# Card4to16.net
KiCad netlist of a schematic drawn in EAGLE
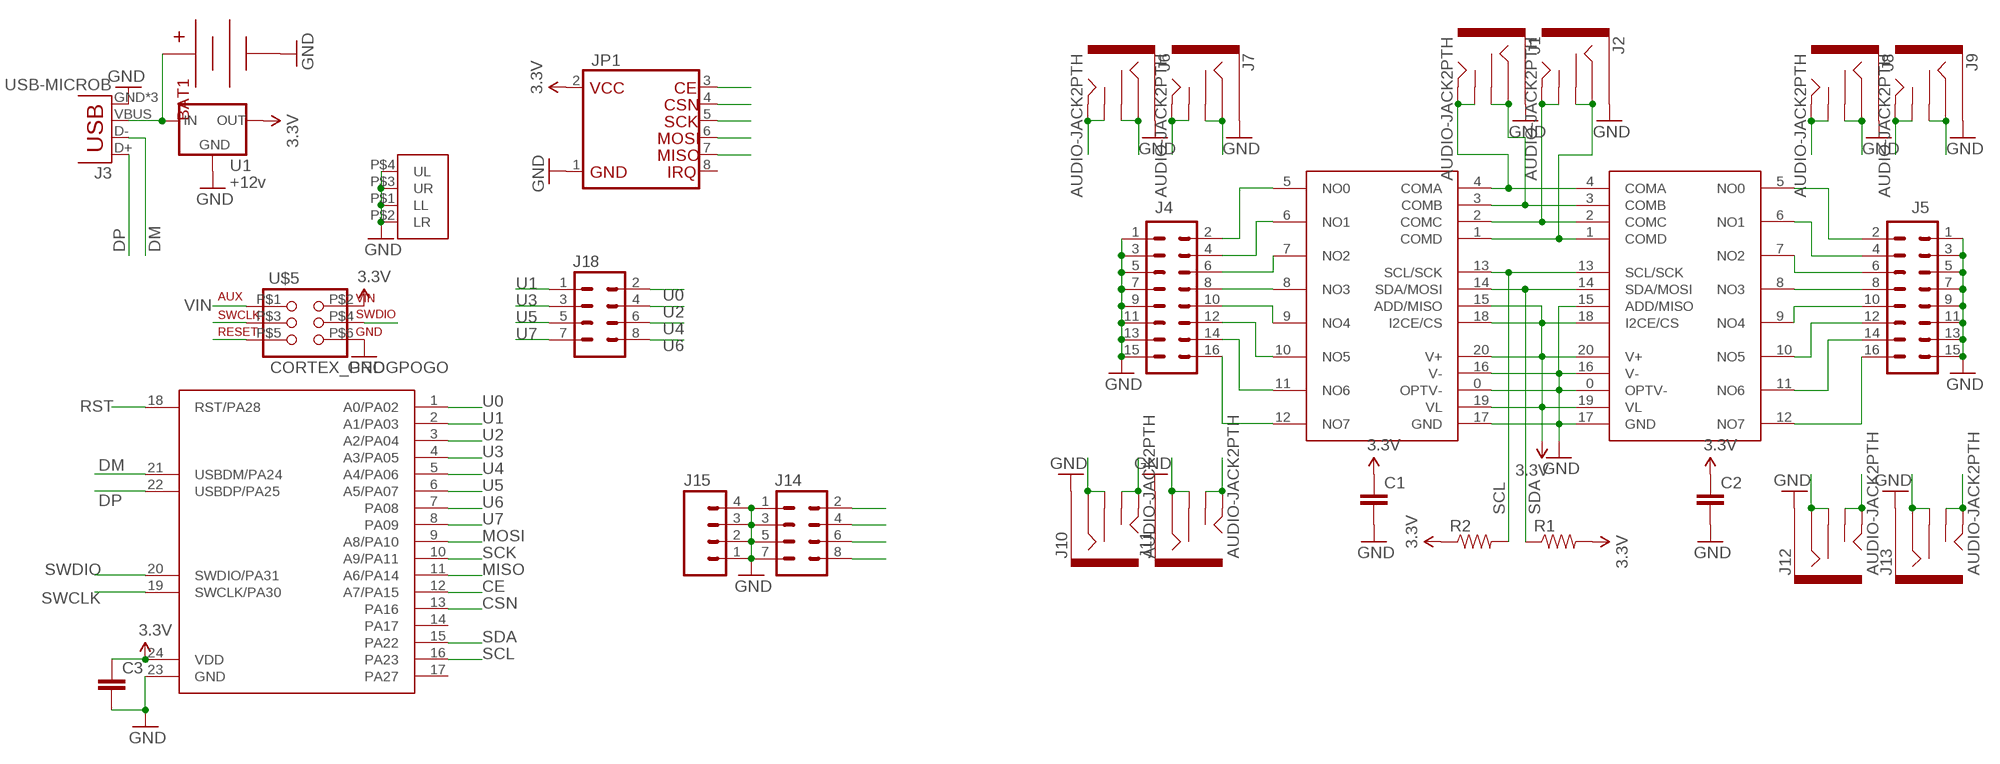
[diagram p0: schematic, sheet 1]

(export (version "E")
  (design (tool "Eeschema 10.0.6"))
  (components
    (comp (ref "BAT1")
      (value "9VHOLDERCLIPS")
      (footprint "eagle-import:BSPC9V")
      (libsource (lib "eagle-import") (part "9VHOLDERCLIPS"))
    )
    (comp (ref "C1")
      (value "CAP0805")
      (footprint "eagle-import:0805")
      (libsource (lib "eagle-import") (part "CAP0805"))
    )
    (comp (ref "C2")
      (value "CAP0805")
      (footprint "eagle-import:0805")
      (libsource (lib "eagle-import") (part "CAP0805"))
    )
    (comp (ref "C3")
      (value "CAP0805")
      (footprint "eagle-import:0805")
      (libsource (lib "eagle-import") (part "CAP0805"))
    )
    (comp (ref "J1")
      (value "AUDIO-JACK2PTH")
      (footprint "eagle-import:AUDIO-JACK")
      (libsource (lib "eagle-import") (part "AUDIO-JACK2PTH"))
    )
    (comp (ref "J2")
      (value "AUDIO-JACK2PTH")
      (footprint "eagle-import:AUDIO-JACK")
      (libsource (lib "eagle-import") (part "AUDIO-JACK2PTH"))
    )
    (comp (ref "J3")
      (value "USB-MICROB")
      (footprint "eagle-import:USB-MICROB")
      (libsource (lib "eagle-import") (part "USB-MICROB"))
    )
    (comp (ref "J4")
      (value "M08X2")
      (footprint "eagle-import:2X8")
      (libsource (lib "eagle-import") (part "M08X2"))
    )
    (comp (ref "J5")
      (value "M08X2")
      (footprint "eagle-import:2X8")
      (libsource (lib "eagle-import") (part "M08X2"))
    )
    (comp (ref "J6")
      (value "AUDIO-JACK2PTH")
      (footprint "eagle-import:AUDIO-JACK")
      (libsource (lib "eagle-import") (part "AUDIO-JACK2PTH"))
    )
    (comp (ref "J7")
      (value "AUDIO-JACK2PTH")
      (footprint "eagle-import:AUDIO-JACK")
      (libsource (lib "eagle-import") (part "AUDIO-JACK2PTH"))
    )
    (comp (ref "J8")
      (value "AUDIO-JACK2PTH")
      (footprint "eagle-import:AUDIO-JACK")
      (libsource (lib "eagle-import") (part "AUDIO-JACK2PTH"))
    )
    (comp (ref "J9")
      (value "AUDIO-JACK2PTH")
      (footprint "eagle-import:AUDIO-JACK")
      (libsource (lib "eagle-import") (part "AUDIO-JACK2PTH"))
    )
    (comp (ref "J10")
      (value "AUDIO-JACK2PTH")
      (footprint "eagle-import:AUDIO-JACK")
      (libsource (lib "eagle-import") (part "AUDIO-JACK2PTH"))
    )
    (comp (ref "J11")
      (value "AUDIO-JACK2PTH")
      (footprint "eagle-import:AUDIO-JACK")
      (libsource (lib "eagle-import") (part "AUDIO-JACK2PTH"))
    )
    (comp (ref "J12")
      (value "AUDIO-JACK2PTH")
      (footprint "eagle-import:AUDIO-JACK")
      (libsource (lib "eagle-import") (part "AUDIO-JACK2PTH"))
    )
    (comp (ref "J13")
      (value "AUDIO-JACK2PTH")
      (footprint "eagle-import:AUDIO-JACK")
      (libsource (lib "eagle-import") (part "AUDIO-JACK2PTH"))
    )
    (comp (ref "J14")
      (value "M04X2")
      (footprint "eagle-import:2X4")
      (libsource (lib "eagle-import") (part "M04X2"))
    )
    (comp (ref "J15")
      (value "M04PTH")
      (footprint "eagle-import:1X04")
      (libsource (lib "eagle-import") (part "M04PTH"))
    )
    (comp (ref "J18")
      (value "M04X2")
      (footprint "eagle-import:2X4")
      (libsource (lib "eagle-import") (part "M04X2"))
    )
    (comp (ref "JP1")
      (value "NRF24L01+SHORT_FLUSH")
      (footprint "eagle-import:NRF24L01SHORT")
      (libsource (lib "eagle-import") (part "NRF24L01+SHORT_FLUSH"))
    )
    (comp (ref "R1")
      (value "RESISTOR0603-RES")
      (footprint "eagle-import:0603-RES")
      (libsource (lib "eagle-import") (part "RESISTOR0603-RES"))
    )
    (comp (ref "R2")
      (value "RESISTOR0603-RES")
      (footprint "eagle-import:0603-RES")
      (libsource (lib "eagle-import") (part "RESISTOR0603-RES"))
    )
    (comp (ref "U$1")
      (value "MAX14724ETP+QFN")
      (footprint "eagle-import:QFN20_4X4")
      (libsource (lib "eagle-import") (part "MAX14724ETP+QFN"))
    )
    (comp (ref "U$2")
      (value "MAX14724ETP+QFN")
      (footprint "eagle-import:QFN20_4X4")
      (libsource (lib "eagle-import") (part "MAX14724ETP+QFN"))
    )
    (comp (ref "U$3")
      (value "ATSAMD11D14A-M")
      (footprint "eagle-import:QFN24_4X4")
      (libsource (lib "eagle-import") (part "ATSAMD11D14A-M"))
    )
    (comp (ref "U$4")
      (value "CARD_HOLESHOLES")
      (footprint "eagle-import:IEC-7810_ID-1_HOLES")
      (libsource (lib "eagle-import") (part "CARD_HOLESHOLES"))
    )
    (comp (ref "U$5")
      (value "CORTEX_PROGPOGO")
      (footprint "eagle-import:2X3_MAX")
      (libsource (lib "eagle-import") (part "CORTEX_PROGPOGO"))
    )
    (comp (ref "U1")
      (value "+12v")
      (footprint "eagle-import:TO-252")
      (libsource (lib "eagle-import") (part "V_REG_78XX7812"))
    )
  )
  (nets
    (net (code "1") (name "/CE") (class "Default")
      (node (ref "JP1") (pin "3") (pinfunction "CE_3") (pintype "passive"))
      (node (ref "U$3") (pin "12") (pinfunction "A7/PA15_12") (pintype "bidirectional"))
    )
    (net (code "2") (name "/COMA") (class "Default")
      (node (ref "J1") (pin "TIP") (pinfunction "TIP_TIP") (pintype "bidirectional"))
      (node (ref "J1") (pin "TSH") (pinfunction "TSH_TSH") (pintype "bidirectional"))
      (node (ref "J14") (pin "2") (pinfunction "2_2") (pintype "passive"))
      (node (ref "U$1") (pin "4") (pinfunction "COMA_4") (pintype "bidirectional"))
      (node (ref "U$2") (pin "4") (pinfunction "COMA_4") (pintype "bidirectional"))
    )
    (net (code "3") (name "/COMB") (class "Default")
      (node (ref "J1") (pin "RING") (pinfunction "RING_RING") (pintype "bidirectional"))
      (node (ref "J1") (pin "RSH") (pinfunction "RSH_RSH") (pintype "bidirectional"))
      (node (ref "J14") (pin "4") (pinfunction "4_4") (pintype "passive"))
      (node (ref "U$1") (pin "3") (pinfunction "COMB_3") (pintype "bidirectional"))
      (node (ref "U$2") (pin "3") (pinfunction "COMB_3") (pintype "bidirectional"))
    )
    (net (code "4") (name "/COMC") (class "Default")
      (node (ref "J14") (pin "6") (pinfunction "6_6") (pintype "passive"))
      (node (ref "J2") (pin "TIP") (pinfunction "TIP_TIP") (pintype "bidirectional"))
      (node (ref "J2") (pin "TSH") (pinfunction "TSH_TSH") (pintype "bidirectional"))
      (node (ref "U$1") (pin "2") (pinfunction "COMC_2") (pintype "bidirectional"))
      (node (ref "U$2") (pin "2") (pinfunction "COMC_2") (pintype "bidirectional"))
    )
    (net (code "5") (name "/COMD") (class "Default")
      (node (ref "J14") (pin "8") (pinfunction "8_8") (pintype "passive"))
      (node (ref "J2") (pin "RING") (pinfunction "RING_RING") (pintype "bidirectional"))
      (node (ref "J2") (pin "RSH") (pinfunction "RSH_RSH") (pintype "bidirectional"))
      (node (ref "U$1") (pin "1") (pinfunction "COMD_1") (pintype "bidirectional"))
      (node (ref "U$2") (pin "1") (pinfunction "COMD_1") (pintype "bidirectional"))
    )
    (net (code "6") (name "/CSN") (class "Default")
      (node (ref "JP1") (pin "4") (pinfunction "CSN_4") (pintype "passive"))
      (node (ref "U$3") (pin "13") (pinfunction "PA16_13") (pintype "bidirectional"))
    )
    (net (code "7") (name "/DM") (class "Default")
      (node (ref "J3") (pin "D-") (pinfunction "D-_D-") (pintype "bidirectional"))
      (node (ref "U$3") (pin "21") (pinfunction "USBDM/PA24_21") (pintype "bidirectional"))
    )
    (net (code "8") (name "/DP") (class "Default")
      (node (ref "J3") (pin "D+") (pinfunction "D+_D+") (pintype "bidirectional"))
      (node (ref "U$3") (pin "22") (pinfunction "USBDP/PA25_22") (pintype "bidirectional"))
    )
    (net (code "9") (name "/MISO") (class "Default")
      (node (ref "JP1") (pin "7") (pinfunction "MISO_7") (pintype "passive"))
      (node (ref "U$3") (pin "11") (pinfunction "A6/PA14_11") (pintype "bidirectional"))
    )
    (net (code "10") (name "/MOSI") (class "Default")
      (node (ref "JP1") (pin "6") (pinfunction "MOSI_6") (pintype "passive"))
      (node (ref "U$3") (pin "9") (pinfunction "A8/PA10_9") (pintype "bidirectional"))
    )
    (net (code "11") (name "/OUT1") (class "Default")
      (node (ref "J10") (pin "RING") (pinfunction "RING_RING") (pintype "bidirectional"))
      (node (ref "J10") (pin "RSH") (pinfunction "RSH_RSH") (pintype "bidirectional"))
      (node (ref "J4") (pin "2") (pinfunction "2_2") (pintype "passive"))
      (node (ref "U$1") (pin "5") (pinfunction "NO0_5") (pintype "bidirectional"))
    )
    (net (code "12") (name "/OUT2") (class "Default")
      (node (ref "J10") (pin "TIP") (pinfunction "TIP_TIP") (pintype "bidirectional"))
      (node (ref "J10") (pin "TSH") (pinfunction "TSH_TSH") (pintype "bidirectional"))
      (node (ref "J4") (pin "4") (pinfunction "4_4") (pintype "passive"))
      (node (ref "U$1") (pin "6") (pinfunction "NO1_6") (pintype "bidirectional"))
    )
    (net (code "13") (name "/OUT3") (class "Default")
      (node (ref "J11") (pin "RING") (pinfunction "RING_RING") (pintype "bidirectional"))
      (node (ref "J11") (pin "RSH") (pinfunction "RSH_RSH") (pintype "bidirectional"))
      (node (ref "J4") (pin "6") (pinfunction "6_6") (pintype "passive"))
      (node (ref "U$1") (pin "7") (pinfunction "NO2_7") (pintype "bidirectional"))
    )
    (net (code "14") (name "/OUT4") (class "Default")
      (node (ref "J11") (pin "TIP") (pinfunction "TIP_TIP") (pintype "bidirectional"))
      (node (ref "J11") (pin "TSH") (pinfunction "TSH_TSH") (pintype "bidirectional"))
      (node (ref "J4") (pin "8") (pinfunction "8_8") (pintype "passive"))
      (node (ref "U$1") (pin "8") (pinfunction "NO3_8") (pintype "bidirectional"))
    )
    (net (code "15") (name "/OUT5") (class "Default")
      (node (ref "J12") (pin "RING") (pinfunction "RING_RING") (pintype "bidirectional"))
      (node (ref "J12") (pin "RSH") (pinfunction "RSH_RSH") (pintype "bidirectional"))
      (node (ref "J4") (pin "10") (pinfunction "10_10") (pintype "passive"))
      (node (ref "U$1") (pin "9") (pinfunction "NO4_9") (pintype "bidirectional"))
    )
    (net (code "16") (name "/OUT6") (class "Default")
      (node (ref "J12") (pin "TIP") (pinfunction "TIP_TIP") (pintype "bidirectional"))
      (node (ref "J12") (pin "TSH") (pinfunction "TSH_TSH") (pintype "bidirectional"))
      (node (ref "J4") (pin "12") (pinfunction "12_12") (pintype "passive"))
      (node (ref "U$1") (pin "10") (pinfunction "NO5_10") (pintype "bidirectional"))
    )
    (net (code "17") (name "/OUT7") (class "Default")
      (node (ref "J13") (pin "RING") (pinfunction "RING_RING") (pintype "bidirectional"))
      (node (ref "J13") (pin "RSH") (pinfunction "RSH_RSH") (pintype "bidirectional"))
      (node (ref "J4") (pin "14") (pinfunction "14_14") (pintype "passive"))
      (node (ref "U$1") (pin "11") (pinfunction "NO6_11") (pintype "bidirectional"))
    )
    (net (code "18") (name "/OUT8") (class "Default")
      (node (ref "J13") (pin "TIP") (pinfunction "TIP_TIP") (pintype "bidirectional"))
      (node (ref "J13") (pin "TSH") (pinfunction "TSH_TSH") (pintype "bidirectional"))
      (node (ref "J4") (pin "16") (pinfunction "16_16") (pintype "passive"))
      (node (ref "U$1") (pin "12") (pinfunction "NO7_12") (pintype "bidirectional"))
    )
    (net (code "19") (name "/OUT9") (class "Default")
      (node (ref "J5") (pin "2") (pinfunction "2_2") (pintype "passive"))
      (node (ref "J6") (pin "RING") (pinfunction "RING_RING") (pintype "bidirectional"))
      (node (ref "J6") (pin "RSH") (pinfunction "RSH_RSH") (pintype "bidirectional"))
      (node (ref "U$2") (pin "5") (pinfunction "NO0_5") (pintype "bidirectional"))
    )
    (net (code "20") (name "/OUT10") (class "Default")
      (node (ref "J5") (pin "4") (pinfunction "4_4") (pintype "passive"))
      (node (ref "J6") (pin "TIP") (pinfunction "TIP_TIP") (pintype "bidirectional"))
      (node (ref "J6") (pin "TSH") (pinfunction "TSH_TSH") (pintype "bidirectional"))
      (node (ref "U$2") (pin "6") (pinfunction "NO1_6") (pintype "bidirectional"))
    )
    (net (code "21") (name "/OUT11") (class "Default")
      (node (ref "J5") (pin "6") (pinfunction "6_6") (pintype "passive"))
      (node (ref "J7") (pin "RING") (pinfunction "RING_RING") (pintype "bidirectional"))
      (node (ref "J7") (pin "RSH") (pinfunction "RSH_RSH") (pintype "bidirectional"))
      (node (ref "U$2") (pin "7") (pinfunction "NO2_7") (pintype "bidirectional"))
    )
    (net (code "22") (name "/OUT12") (class "Default")
      (node (ref "J5") (pin "8") (pinfunction "8_8") (pintype "passive"))
      (node (ref "J7") (pin "TIP") (pinfunction "TIP_TIP") (pintype "bidirectional"))
      (node (ref "J7") (pin "TSH") (pinfunction "TSH_TSH") (pintype "bidirectional"))
      (node (ref "U$2") (pin "8") (pinfunction "NO3_8") (pintype "bidirectional"))
    )
    (net (code "23") (name "/OUT13") (class "Default")
      (node (ref "J5") (pin "10") (pinfunction "10_10") (pintype "passive"))
      (node (ref "J8") (pin "RING") (pinfunction "RING_RING") (pintype "bidirectional"))
      (node (ref "J8") (pin "RSH") (pinfunction "RSH_RSH") (pintype "bidirectional"))
      (node (ref "U$2") (pin "9") (pinfunction "NO4_9") (pintype "bidirectional"))
    )
    (net (code "24") (name "/OUT14") (class "Default")
      (node (ref "J5") (pin "12") (pinfunction "12_12") (pintype "passive"))
      (node (ref "J8") (pin "TIP") (pinfunction "TIP_TIP") (pintype "bidirectional"))
      (node (ref "J8") (pin "TSH") (pinfunction "TSH_TSH") (pintype "bidirectional"))
      (node (ref "U$2") (pin "10") (pinfunction "NO5_10") (pintype "bidirectional"))
    )
    (net (code "25") (name "/OUT15") (class "Default")
      (node (ref "J5") (pin "14") (pinfunction "14_14") (pintype "passive"))
      (node (ref "J9") (pin "RING") (pinfunction "RING_RING") (pintype "bidirectional"))
      (node (ref "J9") (pin "RSH") (pinfunction "RSH_RSH") (pintype "bidirectional"))
      (node (ref "U$2") (pin "11") (pinfunction "NO6_11") (pintype "bidirectional"))
    )
    (net (code "26") (name "/OUT16") (class "Default")
      (node (ref "J5") (pin "16") (pinfunction "16_16") (pintype "passive"))
      (node (ref "J9") (pin "TIP") (pinfunction "TIP_TIP") (pintype "bidirectional"))
      (node (ref "J9") (pin "TSH") (pinfunction "TSH_TSH") (pintype "bidirectional"))
      (node (ref "U$2") (pin "12") (pinfunction "NO7_12") (pintype "bidirectional"))
    )
    (net (code "27") (name "/RST") (class "Default")
      (node (ref "U$3") (pin "18") (pinfunction "RST/PA28_18") (pintype "bidirectional"))
      (node (ref "U$5") (pin "P$5") (pinfunction "RST_P$5") (pintype "passive"))
    )
    (net (code "28") (name "/SCK") (class "Default")
      (node (ref "JP1") (pin "5") (pinfunction "SCK_5") (pintype "passive"))
      (node (ref "U$3") (pin "10") (pinfunction "A9/PA11_10") (pintype "bidirectional"))
    )
    (net (code "29") (name "/SCL") (class "Default")
      (node (ref "R2") (pin "2") (pinfunction "2_2") (pintype "passive"))
      (node (ref "U$1") (pin "13") (pinfunction "SCL/SCK_13") (pintype "bidirectional"))
      (node (ref "U$2") (pin "13") (pinfunction "SCL/SCK_13") (pintype "bidirectional"))
      (node (ref "U$3") (pin "16") (pinfunction "PA23_16") (pintype "bidirectional"))
    )
    (net (code "30") (name "/SDA") (class "Default")
      (node (ref "R1") (pin "1") (pinfunction "1_1") (pintype "passive"))
      (node (ref "U$1") (pin "14") (pinfunction "SDA/MOSI_14") (pintype "bidirectional"))
      (node (ref "U$2") (pin "14") (pinfunction "SDA/MOSI_14") (pintype "bidirectional"))
      (node (ref "U$3") (pin "15") (pinfunction "PA22_15") (pintype "bidirectional"))
    )
    (net (code "31") (name "/SWCLK") (class "Default")
      (node (ref "U$3") (pin "19") (pinfunction "SWCLK/PA30_19") (pintype "bidirectional"))
      (node (ref "U$5") (pin "P$3") (pinfunction "SWCLK_P$3") (pintype "passive"))
    )
    (net (code "32") (name "/SWDIO") (class "Default")
      (node (ref "U$3") (pin "20") (pinfunction "SWDIO/PA31_20") (pintype "bidirectional"))
      (node (ref "U$5") (pin "P$4") (pinfunction "SWDIO_P$4") (pintype "passive"))
    )
    (net (code "33") (name "/U0") (class "Default")
      (node (ref "J18") (pin "2") (pinfunction "2_2") (pintype "passive"))
      (node (ref "U$3") (pin "1") (pinfunction "A0/PA02_1") (pintype "bidirectional"))
    )
    (net (code "34") (name "/U1") (class "Default")
      (node (ref "J18") (pin "1") (pinfunction "1_1") (pintype "passive"))
      (node (ref "U$3") (pin "2") (pinfunction "A1/PA03_2") (pintype "bidirectional"))
    )
    (net (code "35") (name "/U2") (class "Default")
      (node (ref "J18") (pin "4") (pinfunction "4_4") (pintype "passive"))
      (node (ref "U$3") (pin "3") (pinfunction "A2/PA04_3") (pintype "bidirectional"))
    )
    (net (code "36") (name "/U3") (class "Default")
      (node (ref "J18") (pin "3") (pinfunction "3_3") (pintype "passive"))
      (node (ref "U$3") (pin "4") (pinfunction "A3/PA05_4") (pintype "bidirectional"))
    )
    (net (code "37") (name "/U4") (class "Default")
      (node (ref "J18") (pin "6") (pinfunction "6_6") (pintype "passive"))
      (node (ref "U$3") (pin "5") (pinfunction "A4/PA06_5") (pintype "bidirectional"))
    )
    (net (code "38") (name "/U5") (class "Default")
      (node (ref "J18") (pin "5") (pinfunction "5_5") (pintype "passive"))
      (node (ref "U$3") (pin "6") (pinfunction "A5/PA07_6") (pintype "bidirectional"))
    )
    (net (code "39") (name "/U6") (class "Default")
      (node (ref "J18") (pin "8") (pinfunction "8_8") (pintype "passive"))
      (node (ref "U$3") (pin "7") (pinfunction "PA08_7") (pintype "bidirectional"))
    )
    (net (code "40") (name "/U7") (class "Default")
      (node (ref "J18") (pin "7") (pinfunction "7_7") (pintype "passive"))
      (node (ref "U$3") (pin "8") (pinfunction "PA09_8") (pintype "bidirectional"))
    )
    (net (code "41") (name "/VIN") (class "Default")
      (node (ref "BAT1") (pin "P$4") (pinfunction "V+_P$4") (pintype "bidirectional"))
      (node (ref "BAT1") (pin "P$5") (pinfunction "V+_P$5") (pintype "bidirectional"))
      (node (ref "BAT1") (pin "P$6") (pinfunction "V+_P$6") (pintype "bidirectional"))
      (node (ref "J3") (pin "VBUS") (pinfunction "VBUS_VBUS") (pintype "bidirectional"))
      (node (ref "U$5") (pin "P$1") (pinfunction "AUX_P$1") (pintype "passive"))
      (node (ref "U1") (pin "1") (pinfunction "IN_1") (pintype "input"))
    )
    (net (code "42") (name "3.3V") (class "Default")
      (node (ref "C1") (pin "1") (pinfunction "1_1") (pintype "passive"))
      (node (ref "C2") (pin "1") (pinfunction "1_1") (pintype "passive"))
      (node (ref "C3") (pin "1") (pinfunction "1_1") (pintype "passive"))
      (node (ref "JP1") (pin "2") (pinfunction "VCC_2") (pintype "passive"))
      (node (ref "R1") (pin "2") (pinfunction "2_2") (pintype "passive"))
      (node (ref "R2") (pin "1") (pinfunction "1_1") (pintype "passive"))
      (node (ref "U$1") (pin "15") (pinfunction "ADD/MISO_15") (pintype "bidirectional"))
      (node (ref "U$1") (pin "18") (pinfunction "I2CE/CS_18") (pintype "bidirectional"))
      (node (ref "U$1") (pin "19") (pinfunction "VL_19") (pintype "bidirectional"))
      (node (ref "U$1") (pin "20") (pinfunction "V+_20") (pintype "bidirectional"))
      (node (ref "U$2") (pin "18") (pinfunction "I2CE/CS_18") (pintype "bidirectional"))
      (node (ref "U$2") (pin "19") (pinfunction "VL_19") (pintype "bidirectional"))
      (node (ref "U$2") (pin "20") (pinfunction "V+_20") (pintype "bidirectional"))
      (node (ref "U$3") (pin "24") (pinfunction "VDD_24") (pintype "bidirectional"))
      (node (ref "U$5") (pin "P$2") (pinfunction "VIN_P$2") (pintype "passive"))
      (node (ref "U1") (pin "2") (pinfunction "OUT_2") (pintype "passive"))
    )
    (net (code "43") (name "GND") (class "Default")
      (node (ref "BAT1") (pin "P$1") (pinfunction "V-_P$1") (pintype "bidirectional"))
      (node (ref "BAT1") (pin "P$2") (pinfunction "V-_P$2") (pintype "bidirectional"))
      (node (ref "BAT1") (pin "P$3") (pinfunction "V-_P$3") (pintype "bidirectional"))
      (node (ref "C1") (pin "2") (pinfunction "2_2") (pintype "passive"))
      (node (ref "C2") (pin "2") (pinfunction "2_2") (pintype "passive"))
      (node (ref "C3") (pin "2") (pinfunction "2_2") (pintype "passive"))
      (node (ref "J1") (pin "SLEEVE") (pinfunction "SLEEVE_SLEEVE") (pintype "bidirectional"))
      (node (ref "J10") (pin "SLEEVE") (pinfunction "SLEEVE_SLEEVE") (pintype "bidirectional"))
      (node (ref "J11") (pin "SLEEVE") (pinfunction "SLEEVE_SLEEVE") (pintype "bidirectional"))
      (node (ref "J12") (pin "SLEEVE") (pinfunction "SLEEVE_SLEEVE") (pintype "bidirectional"))
      (node (ref "J13") (pin "SLEEVE") (pinfunction "SLEEVE_SLEEVE") (pintype "bidirectional"))
      (node (ref "J14") (pin "1") (pinfunction "1_1") (pintype "passive"))
      (node (ref "J14") (pin "3") (pinfunction "3_3") (pintype "passive"))
      (node (ref "J14") (pin "5") (pinfunction "5_5") (pintype "passive"))
      (node (ref "J14") (pin "7") (pinfunction "7_7") (pintype "passive"))
      (node (ref "J15") (pin "1") (pinfunction "1_1") (pintype "passive"))
      (node (ref "J15") (pin "2") (pinfunction "2_2") (pintype "passive"))
      (node (ref "J15") (pin "3") (pinfunction "3_3") (pintype "passive"))
      (node (ref "J15") (pin "4") (pinfunction "4_4") (pintype "passive"))
      (node (ref "J2") (pin "SLEEVE") (pinfunction "SLEEVE_SLEEVE") (pintype "bidirectional"))
      (node (ref "J3") (pin "GND") (pinfunction "GND_GND") (pintype "bidirectional"))
      (node (ref "J3") (pin "MT1") (pinfunction "GND_MT1") (pintype "bidirectional"))
      (node (ref "J3") (pin "MT2") (pinfunction "GND_MT2") (pintype "bidirectional"))
      (node (ref "J4") (pin "1") (pinfunction "1_1") (pintype "passive"))
      (node (ref "J4") (pin "11") (pinfunction "11_11") (pintype "passive"))
      (node (ref "J4") (pin "13") (pinfunction "13_13") (pintype "passive"))
      (node (ref "J4") (pin "15") (pinfunction "15_15") (pintype "passive"))
      (node (ref "J4") (pin "3") (pinfunction "3_3") (pintype "passive"))
      (node (ref "J4") (pin "5") (pinfunction "5_5") (pintype "passive"))
      (node (ref "J4") (pin "7") (pinfunction "7_7") (pintype "passive"))
      (node (ref "J4") (pin "9") (pinfunction "9_9") (pintype "passive"))
      (node (ref "J5") (pin "1") (pinfunction "1_1") (pintype "passive"))
      (node (ref "J5") (pin "11") (pinfunction "11_11") (pintype "passive"))
      (node (ref "J5") (pin "13") (pinfunction "13_13") (pintype "passive"))
      (node (ref "J5") (pin "15") (pinfunction "15_15") (pintype "passive"))
      (node (ref "J5") (pin "3") (pinfunction "3_3") (pintype "passive"))
      (node (ref "J5") (pin "5") (pinfunction "5_5") (pintype "passive"))
      (node (ref "J5") (pin "7") (pinfunction "7_7") (pintype "passive"))
      (node (ref "J5") (pin "9") (pinfunction "9_9") (pintype "passive"))
      (node (ref "J6") (pin "SLEEVE") (pinfunction "SLEEVE_SLEEVE") (pintype "bidirectional"))
      (node (ref "J7") (pin "SLEEVE") (pinfunction "SLEEVE_SLEEVE") (pintype "bidirectional"))
      (node (ref "J8") (pin "SLEEVE") (pinfunction "SLEEVE_SLEEVE") (pintype "bidirectional"))
      (node (ref "J9") (pin "SLEEVE") (pinfunction "SLEEVE_SLEEVE") (pintype "bidirectional"))
      (node (ref "JP1") (pin "1") (pinfunction "GND_1") (pintype "passive"))
      (node (ref "U$1") (pin "0") (pinfunction "OPTV-_0") (pintype "bidirectional"))
      (node (ref "U$1") (pin "16") (pinfunction "V-_16") (pintype "bidirectional"))
      (node (ref "U$1") (pin "17") (pinfunction "GND_17") (pintype "bidirectional"))
      (node (ref "U$2") (pin "0") (pinfunction "OPTV-_0") (pintype "bidirectional"))
      (node (ref "U$2") (pin "15") (pinfunction "ADD/MISO_15") (pintype "bidirectional"))
      (node (ref "U$2") (pin "16") (pinfunction "V-_16") (pintype "bidirectional"))
      (node (ref "U$2") (pin "17") (pinfunction "GND_17") (pintype "bidirectional"))
      (node (ref "U$3") (pin "23") (pinfunction "GND_23") (pintype "bidirectional"))
      (node (ref "U$4") (pin "P$1") (pinfunction "LL_P$1") (pintype "bidirectional"))
      (node (ref "U$4") (pin "P$2") (pinfunction "LR_P$2") (pintype "bidirectional"))
      (node (ref "U$4") (pin "P$3") (pinfunction "UR_P$3") (pintype "bidirectional"))
      (node (ref "U$4") (pin "P$4") (pinfunction "UL_P$4") (pintype "bidirectional"))
      (node (ref "U$5") (pin "P$6") (pinfunction "GND_P$6") (pintype "passive"))
      (node (ref "U1") (pin "3") (pinfunction "GND_3") (pintype "input"))
    )
    (net (code "44") (name "unconnected-(JP1-IRQ-Pad8)") (class "Default")
      (node (ref "JP1") (pin "8") (pinfunction "IRQ_8") (pintype "passive"))
    )
    (net (code "45") (name "unconnected-(U$3-PA17-Pad14)") (class "Default")
      (node (ref "U$3") (pin "14") (pinfunction "PA17_14") (pintype "bidirectional"))
    )
    (net (code "46") (name "unconnected-(U$3-PA27-Pad17)") (class "Default")
      (node (ref "U$3") (pin "17") (pinfunction "PA27_17") (pintype "bidirectional"))
    )
  )
)
